# NucleoG031K8Sch.net
KiCad netlist of a schematic drawn in Altium Designer
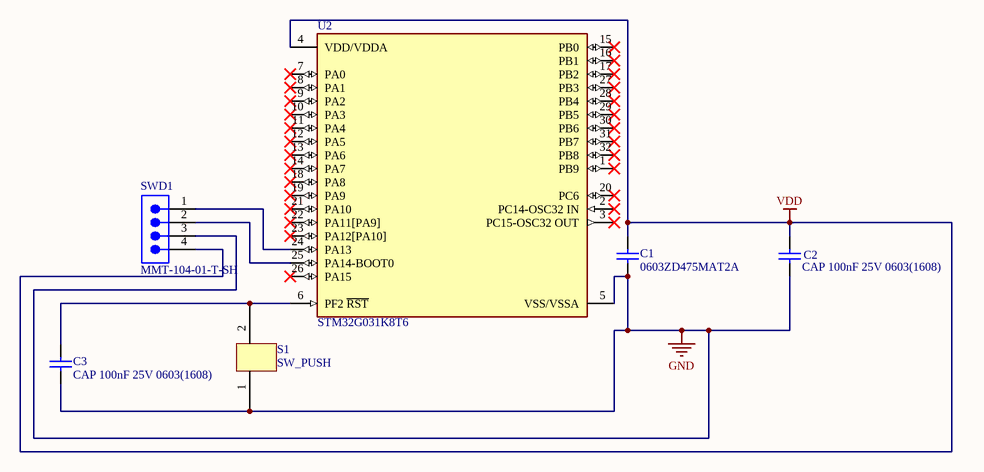
[diagram p0: NucleoG031K8Sch.SchDoc]

(export (version "E")
  (design (tool "Eeschema 10.0.6"))
  (components
    (comp (ref "C1")
      (value "0603ZD475MAT2A")
      (footprint "CAPC1608X90X35NL15T15")
      (fields (field (name "MANUFACTURER") "AVX Interconnect / Elco"))
      (libsource (lib "Altium Content Vault") (part "CAP"))
    )
    (comp (ref "C2")
      (value "CAP 100nF 25V 0603(1608)")
      (footprint "CAPC0603(1608)100_N")
      (description "CAP 100nF 25V ±20% 0603 (1608 Metric) Thickness 1mm SMD")
      (fields (field (name "TOLERANCE") "Â±20%"))
      (libsource (lib "Altium Content Vault") (part "CAP"))
    )
    (comp (ref "C3")
      (value "CAP 100nF 25V 0603(1608)")
      (footprint "CAPC0603(1608)100_N")
      (description "CAP 100nF 25V ±20% 0603 (1608 Metric) Thickness 1mm SMD")
      (fields (field (name "TOLERANCE") "Â±20%"))
      (libsource (lib "Altium Content Vault") (part "CAP"))
    )
    (comp (ref "S1")
      (value "SW_PUSH")
      (footprint "SW_2PIN")
      (libsource (lib "NucleoG031K8Lib") (part "SW_PUSH"))
    )
    (comp (ref "SWD1")
      (value "MMT-104-01-T-SH")
      (footprint "SMTC-MMT-104-01-X-SH")
      (description "Horizontal Surface Mount Header, -55 to 105 degC, 2 mm Pitch, 4-Pin, Male, RoHS")
      (fields (field (name "MANUFACTURER") "Samtec"))
      (libsource (lib "Altium Content Vault") (part "SMTC-MMT-104-X-X-SH"))
    )
    (comp (ref "U2")
      (value "STM32G031K8T6")
      (footprint "FP-LQFP32-5V-MFG")
      (description "IC MCU 32BIT 64KB FLASH 32LQFP")
      (libsource (lib "Altium Content Vault") (part "473aa7f4ee034338f9424f96f5febff"))
    )
  )
  (nets
    (net (code "1") (name "GND") (class "Default")
      (node (ref "C1") (pin "1") (pinfunction "1_1") (pintype "passive"))
      (node (ref "C2") (pin "1") (pinfunction "1_1") (pintype "passive"))
      (node (ref "C3") (pin "1") (pinfunction "1_1") (pintype "passive"))
      (node (ref "S1") (pin "1") (pintype "passive"))
      (node (ref "SWD1") (pin "3") (pinfunction "GND_3") (pintype "passive"))
      (node (ref "U2") (pin "5") (pinfunction "VSS/VSSA_5") (pintype "power_in"))
    )
    (net (code "2") (name "Net-(SWD1-SWDCLK)") (class "Default")
      (node (ref "SWD1") (pin "2") (pinfunction "SWDCLK_2") (pintype "passive"))
      (node (ref "U2") (pin "25") (pinfunction "PA14-BOOT0_25") (pintype "bidirectional"))
    )
    (net (code "3") (name "Net-(SWD1-SWDIO)") (class "Default")
      (node (ref "SWD1") (pin "1") (pinfunction "SWDIO_1") (pintype "passive"))
      (node (ref "U2") (pin "24") (pinfunction "PA13_24") (pintype "bidirectional"))
    )
    (net (code "4") (name "Net-(U2-PF2_~{RST})") (class "Default")
      (node (ref "C3") (pin "2") (pinfunction "2_2") (pintype "passive"))
      (node (ref "S1") (pin "2") (pintype "passive"))
      (node (ref "U2") (pin "6") (pinfunction "PF2_~{RST}_6") (pintype "input"))
    )
    (net (code "5") (name "VDD") (class "Default")
      (node (ref "C1") (pin "2") (pinfunction "2_2") (pintype "passive"))
      (node (ref "C2") (pin "2") (pinfunction "2_2") (pintype "passive"))
      (node (ref "SWD1") (pin "4") (pinfunction "VDD_4") (pintype "passive"))
      (node (ref "U2") (pin "4") (pinfunction "VDD/VDDA_4") (pintype "power_in"))
    )
    (net (code "6") (name "unconnected-(U2-PA0-Pad7)") (class "Default")
      (node (ref "U2") (pin "7") (pinfunction "PA0_7") (pintype "bidirectional+no_connect"))
    )
    (net (code "7") (name "unconnected-(U2-PA1-Pad8)") (class "Default")
      (node (ref "U2") (pin "8") (pinfunction "PA1_8") (pintype "bidirectional+no_connect"))
    )
    (net (code "8") (name "unconnected-(U2-PA2-Pad9)") (class "Default")
      (node (ref "U2") (pin "9") (pinfunction "PA2_9") (pintype "bidirectional+no_connect"))
    )
    (net (code "9") (name "unconnected-(U2-PA3-Pad10)") (class "Default")
      (node (ref "U2") (pin "10") (pinfunction "PA3_10") (pintype "bidirectional+no_connect"))
    )
    (net (code "10") (name "unconnected-(U2-PA4-Pad11)") (class "Default")
      (node (ref "U2") (pin "11") (pinfunction "PA4_11") (pintype "bidirectional+no_connect"))
    )
    (net (code "11") (name "unconnected-(U2-PA5-Pad12)") (class "Default")
      (node (ref "U2") (pin "12") (pinfunction "PA5_12") (pintype "bidirectional+no_connect"))
    )
    (net (code "12") (name "unconnected-(U2-PA6-Pad13)") (class "Default")
      (node (ref "U2") (pin "13") (pinfunction "PA6_13") (pintype "bidirectional+no_connect"))
    )
    (net (code "13") (name "unconnected-(U2-PA7-Pad14)") (class "Default")
      (node (ref "U2") (pin "14") (pinfunction "PA7_14") (pintype "bidirectional+no_connect"))
    )
    (net (code "14") (name "unconnected-(U2-PA8-Pad18)") (class "Default")
      (node (ref "U2") (pin "18") (pinfunction "PA8_18") (pintype "bidirectional+no_connect"))
    )
    (net (code "15") (name "unconnected-(U2-PA9-Pad19)") (class "Default")
      (node (ref "U2") (pin "19") (pinfunction "PA9_19") (pintype "bidirectional+no_connect"))
    )
    (net (code "16") (name "unconnected-(U2-PA10-Pad21)") (class "Default")
      (node (ref "U2") (pin "21") (pinfunction "PA10_21") (pintype "bidirectional+no_connect"))
    )
    (net (code "17") (name "unconnected-(U2-PA11[PA9]-Pad22)") (class "Default")
      (node (ref "U2") (pin "22") (pinfunction "PA11[PA9]_22") (pintype "bidirectional+no_connect"))
    )
    (net (code "18") (name "unconnected-(U2-PA12[PA10]-Pad23)") (class "Default")
      (node (ref "U2") (pin "23") (pinfunction "PA12[PA10]_23") (pintype "bidirectional+no_connect"))
    )
    (net (code "19") (name "unconnected-(U2-PA15-Pad26)") (class "Default")
      (node (ref "U2") (pin "26") (pinfunction "PA15_26") (pintype "bidirectional+no_connect"))
    )
    (net (code "20") (name "unconnected-(U2-PB0-Pad15)") (class "Default")
      (node (ref "U2") (pin "15") (pinfunction "PB0_15") (pintype "bidirectional+no_connect"))
    )
    (net (code "21") (name "unconnected-(U2-PB1-Pad16)") (class "Default")
      (node (ref "U2") (pin "16") (pinfunction "PB1_16") (pintype "bidirectional+no_connect"))
    )
    (net (code "22") (name "unconnected-(U2-PB2-Pad17)") (class "Default")
      (node (ref "U2") (pin "17") (pinfunction "PB2_17") (pintype "bidirectional+no_connect"))
    )
    (net (code "23") (name "unconnected-(U2-PB3-Pad27)") (class "Default")
      (node (ref "U2") (pin "27") (pinfunction "PB3_27") (pintype "bidirectional+no_connect"))
    )
    (net (code "24") (name "unconnected-(U2-PB4-Pad28)") (class "Default")
      (node (ref "U2") (pin "28") (pinfunction "PB4_28") (pintype "bidirectional+no_connect"))
    )
    (net (code "25") (name "unconnected-(U2-PB5-Pad29)") (class "Default")
      (node (ref "U2") (pin "29") (pinfunction "PB5_29") (pintype "bidirectional+no_connect"))
    )
    (net (code "26") (name "unconnected-(U2-PB6-Pad30)") (class "Default")
      (node (ref "U2") (pin "30") (pinfunction "PB6_30") (pintype "bidirectional+no_connect"))
    )
    (net (code "27") (name "unconnected-(U2-PB7-Pad31)") (class "Default")
      (node (ref "U2") (pin "31") (pinfunction "PB7_31") (pintype "bidirectional+no_connect"))
    )
    (net (code "28") (name "unconnected-(U2-PB8-Pad32)") (class "Default")
      (node (ref "U2") (pin "32") (pinfunction "PB8_32") (pintype "bidirectional+no_connect"))
    )
    (net (code "29") (name "unconnected-(U2-PB9-Pad1)") (class "Default")
      (node (ref "U2") (pin "1") (pinfunction "PB9_1") (pintype "bidirectional+no_connect"))
    )
    (net (code "30") (name "unconnected-(U2-PC6-Pad20)") (class "Default")
      (node (ref "U2") (pin "20") (pinfunction "PC6_20") (pintype "bidirectional+no_connect"))
    )
    (net (code "31") (name "unconnected-(U2-PC14-OSC32_IN-Pad2)") (class "Default")
      (node (ref "U2") (pin "2") (pinfunction "PC14-OSC32_IN_2") (pintype "input+no_connect"))
    )
    (net (code "32") (name "unconnected-(U2-PC15-OSC32_OUT-Pad3)") (class "Default")
      (node (ref "U2") (pin "3") (pinfunction "PC15-OSC32_OUT_3") (pintype "output+no_connect"))
    )
  )
)
